# Communication.net
KiCad netlist of a schematic drawn in Altium Designer
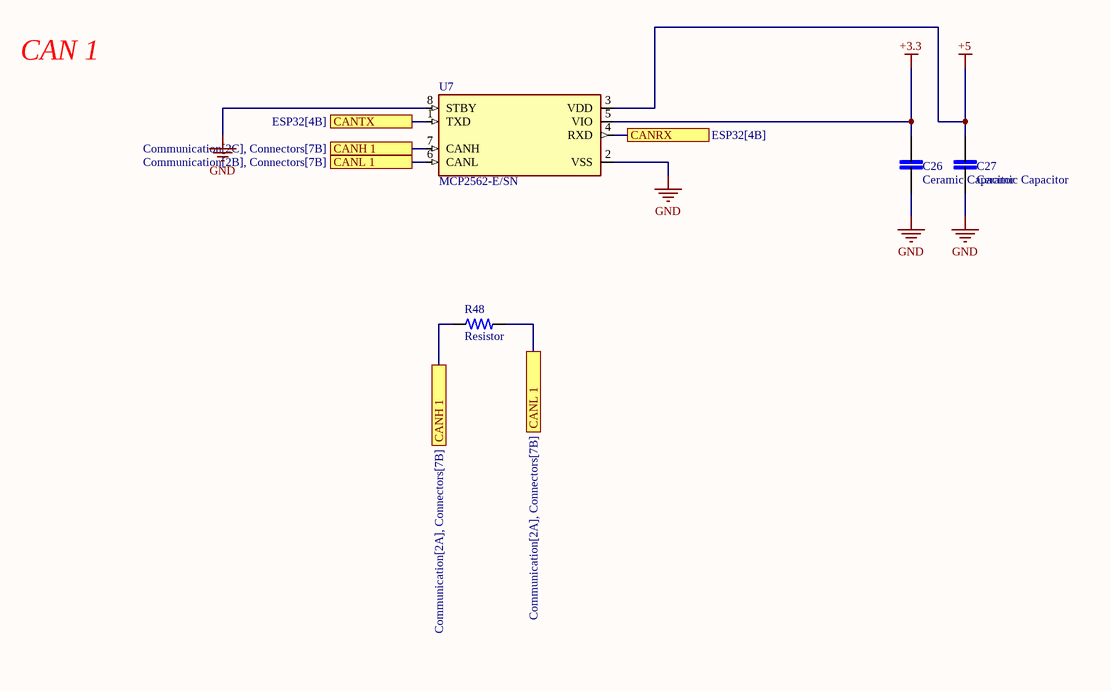
[diagram p0: Communication.SchDoc]

(export (version "E")
  (design (tool "Eeschema 10.0.6"))
  (components
    (comp (ref "C26")
      (value "Ceramic Capacitor")
      (footprint "Ceramic Capacitor")
      (fields (field (name "MP") "LD051A121KAB2A") (field (name "MF") "AVX"))
      (libsource (lib "Capacitors Through Hole") (part "Ceramic Capacitor"))
    )
    (comp (ref "C27")
      (value "Ceramic Capacitor")
      (footprint "Ceramic Capacitor")
      (fields (field (name "MP") "LD051A121KAB2A") (field (name "MF") "AVX"))
      (libsource (lib "Capacitors Through Hole") (part "Ceramic Capacitor"))
    )
    (comp (ref "R48")
      (value "Resistor")
      (footprint "Resistor_Through Hole")
      (fields
        (field (name "MP") "2-2176053-0")
        (field (name "TOLERANCE") "1%")
        (field (name "MF") "TE Connectivity")
      )
      (libsource (lib "Resistors Through Hole") (part "Resistor"))
    )
    (comp (ref "U7")
      (value "MCP2562-E/SN")
      (footprint "Transceiver CAN:MCP2562-E/SN")
      (description "1/1 Transceiver Half CANbus 8-SOIC")
      (fields (field (name "MF") "Microchip"))
      (libsource (lib "Transceiver CAN") (part "MCP2562-E/SN"))
    )
  )
  (nets
    (net (code "1") (name "+3.3") (class "Default")
      (node (ref "C26") (pin "2") (pinfunction "2_2") (pintype "passive"))
      (node (ref "U7") (pin "5") (pinfunction "VIO_5") (pintype "power_in"))
    )
    (net (code "2") (name "+5") (class "Default")
      (node (ref "C27") (pin "2") (pinfunction "2_2") (pintype "passive"))
      (node (ref "U7") (pin "3") (pinfunction "VDD_3") (pintype "power_in"))
    )
    (net (code "3") (name "/CANH 1") (class "Default")
      (node (ref "R48") (pin "1") (pinfunction "1_1") (pintype "passive"))
      (node (ref "U7") (pin "7") (pinfunction "CANH_7") (pintype "input"))
    )
    (net (code "4") (name "/CANL 1") (class "Default")
      (node (ref "R48") (pin "2") (pinfunction "2_2") (pintype "passive"))
      (node (ref "U7") (pin "6") (pinfunction "CANL_6") (pintype "input"))
    )
    (net (code "5") (name "/CANRX") (class "Default")
      (node (ref "U7") (pin "4") (pinfunction "RXD_4") (pintype "output"))
    )
    (net (code "6") (name "/CANTX") (class "Default")
      (node (ref "U7") (pin "1") (pinfunction "TXD_1") (pintype "input"))
    )
    (net (code "7") (name "GND") (class "Default")
      (node (ref "C26") (pin "1") (pinfunction "1_1") (pintype "passive"))
      (node (ref "C27") (pin "1") (pinfunction "1_1") (pintype "passive"))
      (node (ref "U7") (pin "2") (pinfunction "VSS_2") (pintype "power_in"))
      (node (ref "U7") (pin "8") (pinfunction "STBY_8") (pintype "input"))
    )
  )
)
